# Midimiddleman.net
KiCad netlist of a schematic drawn in EAGLE
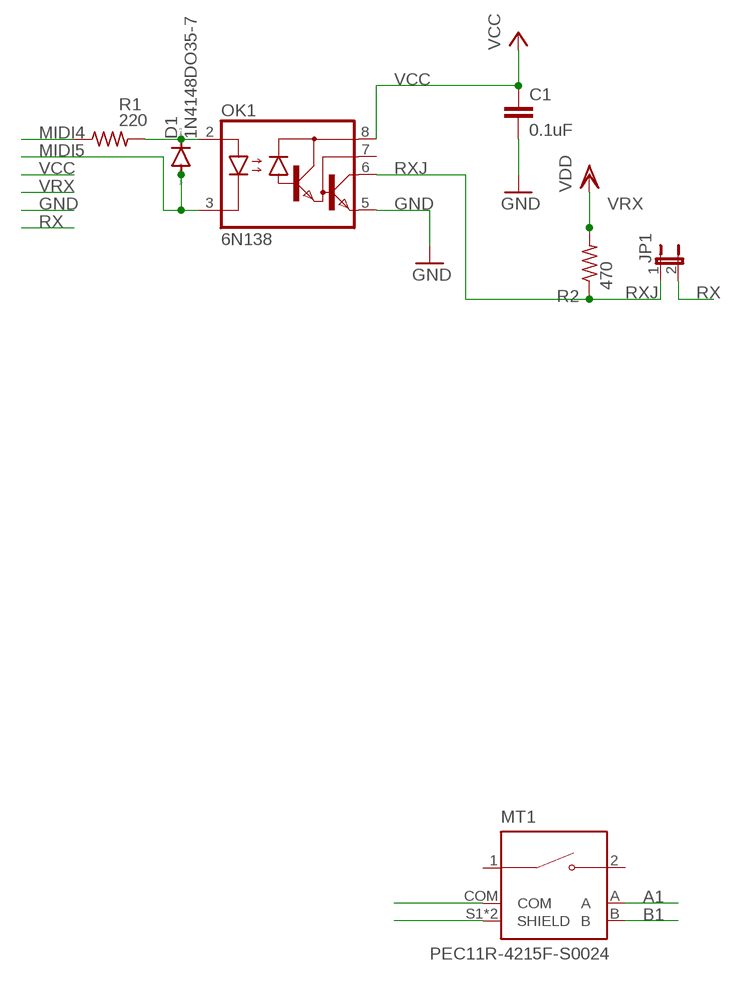
[diagram p0: schematic, sheet 1]

(export (version "E")
  (design (tool "Eeschema 10.0.6"))
  (components
    (comp (ref "C1")
      (value "0.1uF")
      (footprint "eagle-import:C10B5")
      (libsource (lib "eagle-import") (part "C10/5"))
    )
    (comp (ref "D1")
      (value "1N4148DO35-7")
      (footprint "eagle-import:DO35-7")
      (libsource (lib "eagle-import") (part "1N4148DO35-7"))
    )
    (comp (ref "JP1")
      (value "JP1E")
      (footprint "eagle-import:JP1")
      (libsource (lib "eagle-import") (part "JP1E"))
    )
    (comp (ref "MT1")
      (value "PEC11R-4215F-S0024")
      (footprint "eagle-import:XDCR_PEC11R-4215F-S0024")
      (fields (field (name "MF") "Bourns"))
      (libsource (lib "eagle-import") (part "PEC11R-4215F-S0024"))
    )
    (comp (ref "OK1")
      (value "6N138")
      (footprint "eagle-import:DIL08")
      (fields (field (name "MF") "VISHAY/TELEFUNKEN"))
      (libsource (lib "eagle-import") (part "6N138"))
    )
    (comp (ref "R1")
      (value "220")
      (footprint "eagle-import:0207_10")
      (libsource (lib "eagle-import") (part "R-US_0207/10"))
    )
    (comp (ref "R2")
      (value "470")
      (footprint "eagle-import:0207_10")
      (libsource (lib "eagle-import") (part "R-US_0207/10"))
    )
  )
  (nets
    (net (code "1") (name "/A1") (class "Default")
      (node (ref "MT1") (pin "A") (pinfunction "A_A") (pintype "passive"))
    )
    (net (code "2") (name "/B1") (class "Default")
      (node (ref "MT1") (pin "B") (pinfunction "B_B") (pintype "passive"))
    )
    (net (code "3") (name "/MIDI4") (class "Default")
      (node (ref "R1") (pin "1") (pinfunction "1_1") (pintype "passive"))
    )
    (net (code "4") (name "/MIDI5") (class "Default")
      (node (ref "D1") (pin "A") (pinfunction "A_A") (pintype "passive"))
      (node (ref "OK1") (pin "3") (pinfunction "C_3") (pintype "passive"))
    )
    (net (code "5") (name "/RX") (class "Default")
      (node (ref "JP1") (pin "2") (pinfunction "2_2") (pintype "passive"))
    )
    (net (code "6") (name "/RXJ") (class "Default")
      (node (ref "JP1") (pin "1") (pinfunction "1_1") (pintype "passive"))
      (node (ref "OK1") (pin "6") (pinfunction "VO_6") (pintype "passive"))
      (node (ref "R2") (pin "1") (pinfunction "1_1") (pintype "passive"))
    )
    (net (code "7") (name "GND") (class "Default")
      (node (ref "C1") (pin "2") (pinfunction "2_2") (pintype "passive"))
      (node (ref "MT1") (pin "COM") (pinfunction "COM_COM") (pintype "passive"))
      (node (ref "MT1") (pin "S1") (pinfunction "SHIELD_S1") (pintype "passive"))
      (node (ref "MT1") (pin "S2") (pinfunction "SHIELD_S2") (pintype "passive"))
      (node (ref "OK1") (pin "5") (pinfunction "GND_5") (pintype "passive"))
    )
    (net (code "8") (name "Net-(OK1-A)") (class "Default")
      (node (ref "D1") (pin "C") (pinfunction "C_C") (pintype "passive"))
      (node (ref "OK1") (pin "2") (pinfunction "A_2") (pintype "passive"))
      (node (ref "R1") (pin "2") (pinfunction "2_2") (pintype "passive"))
    )
    (net (code "9") (name "VCC") (class "Default")
      (node (ref "C1") (pin "1") (pinfunction "1_1") (pintype "passive"))
      (node (ref "OK1") (pin "8") (pinfunction "VCC_8") (pintype "passive"))
    )
    (net (code "10") (name "VDD") (class "Default")
      (node (ref "R2") (pin "2") (pinfunction "2_2") (pintype "passive"))
    )
    (net (code "11") (name "unconnected-(MT1-Pad1)") (class "Default")
      (node (ref "MT1") (pin "1") (pinfunction "1_1") (pintype "passive"))
    )
    (net (code "12") (name "unconnected-(MT1-Pad2)") (class "Default")
      (node (ref "MT1") (pin "2") (pinfunction "2_2") (pintype "passive"))
    )
    (net (code "13") (name "unconnected-(OK1-VB-Pad7)") (class "Default")
      (node (ref "OK1") (pin "7") (pinfunction "VB_7") (pintype "passive"))
    )
  )
)
